# DEC4.net
KiCad netlist of a schematic drawn in EAGLE
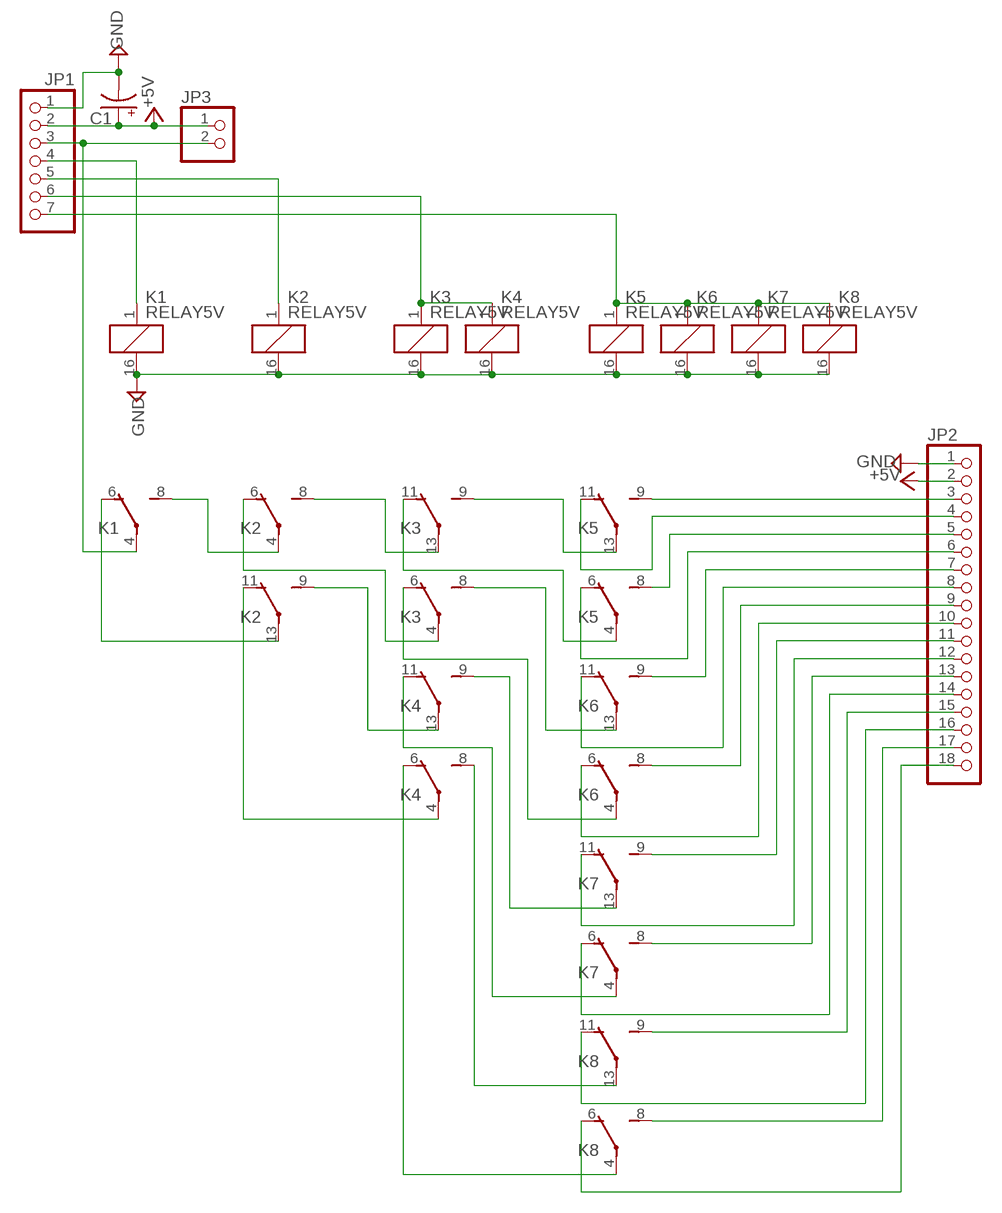
[diagram p0: schematic, sheet 1]

(export (version "E")
  (design (tool "Eeschema 10.0.6"))
  (components
    (comp (ref "C1")
      (value "CC-5-8.5")
      (footprint "eagle-import:E5-8,5")
      (libsource (lib "eagle-import") (part "CC-5-8.5"))
    )
    (comp (ref "JP1")
      (value "PINHD-1X7")
      (footprint "eagle-import:1X07")
      (libsource (lib "eagle-import") (part "PINHD-1X7"))
    )
    (comp (ref "JP2")
      (value "PINHD-1X18")
      (footprint "eagle-import:1X18")
      (libsource (lib "eagle-import") (part "PINHD-1X18"))
    )
    (comp (ref "JP3")
      (value "PINHD-1X2")
      (footprint "eagle-import:1X02")
      (libsource (lib "eagle-import") (part "PINHD-1X2"))
    )
    (comp (ref "K1")
      (value "RELAY5V")
      (footprint "eagle-import:DS-BT")
      (libsource (lib "eagle-import") (part "RELAY5V"))
    )
    (comp (ref "K2")
      (value "RELAY5V")
      (footprint "eagle-import:DS-BT")
      (libsource (lib "eagle-import") (part "RELAY5V"))
    )
    (comp (ref "K3")
      (value "RELAY5V")
      (footprint "eagle-import:DS-BT")
      (libsource (lib "eagle-import") (part "RELAY5V"))
    )
    (comp (ref "K4")
      (value "RELAY5V")
      (footprint "eagle-import:DS-BT")
      (libsource (lib "eagle-import") (part "RELAY5V"))
    )
    (comp (ref "K5")
      (value "RELAY5V")
      (footprint "eagle-import:DS-BT")
      (libsource (lib "eagle-import") (part "RELAY5V"))
    )
    (comp (ref "K6")
      (value "RELAY5V")
      (footprint "eagle-import:DS-BT")
      (libsource (lib "eagle-import") (part "RELAY5V"))
    )
    (comp (ref "K7")
      (value "RELAY5V")
      (footprint "eagle-import:DS-BT")
      (libsource (lib "eagle-import") (part "RELAY5V"))
    )
    (comp (ref "K8")
      (value "RELAY5V")
      (footprint "eagle-import:DS-BT")
      (libsource (lib "eagle-import") (part "RELAY5V"))
    )
  )
  (nets
    (net (code "1") (name "+5V") (class "Default")
      (node (ref "C1") (pin "+") (pinfunction "+_+") (pintype "passive"))
      (node (ref "JP1") (pin "2") (pinfunction "2_2") (pintype "passive"))
      (node (ref "JP2") (pin "2") (pinfunction "2_2") (pintype "passive"))
      (node (ref "JP3") (pin "1") (pinfunction "1_1") (pintype "passive"))
    )
    (net (code "2") (name "GND") (class "Default")
      (node (ref "C1") (pin "-") (pinfunction "-_-") (pintype "passive"))
      (node (ref "JP1") (pin "1") (pinfunction "1_1") (pintype "passive"))
      (node (ref "JP2") (pin "1") (pinfunction "1_1") (pintype "passive"))
      (node (ref "K1") (pin "16") (pinfunction "-_16") (pintype "passive"))
      (node (ref "K2") (pin "16") (pinfunction "-_16") (pintype "passive"))
      (node (ref "K3") (pin "16") (pinfunction "-_16") (pintype "passive"))
      (node (ref "K4") (pin "16") (pinfunction "-_16") (pintype "passive"))
      (node (ref "K5") (pin "16") (pinfunction "-_16") (pintype "passive"))
      (node (ref "K6") (pin "16") (pinfunction "-_16") (pintype "passive"))
      (node (ref "K7") (pin "16") (pinfunction "-_16") (pintype "passive"))
      (node (ref "K8") (pin "16") (pinfunction "-_16") (pintype "passive"))
    )
    (net (code "3") (name "Net-(K1A-+)") (class "Default")
      (node (ref "JP1") (pin "4") (pinfunction "4_4") (pintype "passive"))
      (node (ref "K1") (pin "1") (pinfunction "+_1") (pintype "passive"))
    )
    (net (code "4") (name "Net-(K1B-O)") (class "Default")
      (node (ref "K1") (pin "6") (pinfunction "O_6") (pintype "passive"))
      (node (ref "K2") (pin "13") (pinfunction "P_13") (pintype "passive"))
    )
    (net (code "5") (name "Net-(K1B-P)") (class "Default")
      (node (ref "JP1") (pin "3") (pinfunction "3_3") (pintype "passive"))
      (node (ref "JP3") (pin "2") (pinfunction "2_2") (pintype "passive"))
      (node (ref "K1") (pin "4") (pinfunction "P_4") (pintype "passive"))
    )
    (net (code "6") (name "Net-(K1B-S)") (class "Default")
      (node (ref "K1") (pin "8") (pinfunction "S_8") (pintype "passive"))
      (node (ref "K2") (pin "4") (pinfunction "P_4") (pintype "passive"))
    )
    (net (code "7") (name "Net-(K2A-+)") (class "Default")
      (node (ref "JP1") (pin "5") (pinfunction "5_5") (pintype "passive"))
      (node (ref "K2") (pin "1") (pinfunction "+_1") (pintype "passive"))
    )
    (net (code "8") (name "Net-(K2B-O)") (class "Default")
      (node (ref "K2") (pin "6") (pinfunction "O_6") (pintype "passive"))
      (node (ref "K3") (pin "4") (pinfunction "P_4") (pintype "passive"))
    )
    (net (code "9") (name "Net-(K2B-S)") (class "Default")
      (node (ref "K2") (pin "8") (pinfunction "S_8") (pintype "passive"))
      (node (ref "K3") (pin "13") (pinfunction "P_13") (pintype "passive"))
    )
    (net (code "10") (name "Net-(K2C-O)") (class "Default")
      (node (ref "K2") (pin "11") (pinfunction "O_11") (pintype "passive"))
      (node (ref "K4") (pin "4") (pinfunction "P_4") (pintype "passive"))
    )
    (net (code "11") (name "Net-(K2C-S)") (class "Default")
      (node (ref "K2") (pin "9") (pinfunction "S_9") (pintype "passive"))
      (node (ref "K4") (pin "13") (pinfunction "P_13") (pintype "passive"))
    )
    (net (code "12") (name "Net-(K3A-+)") (class "Default")
      (node (ref "JP1") (pin "6") (pinfunction "6_6") (pintype "passive"))
      (node (ref "K3") (pin "1") (pinfunction "+_1") (pintype "passive"))
      (node (ref "K4") (pin "1") (pinfunction "+_1") (pintype "passive"))
    )
    (net (code "13") (name "Net-(K3B-O)") (class "Default")
      (node (ref "K3") (pin "6") (pinfunction "O_6") (pintype "passive"))
      (node (ref "K6") (pin "4") (pinfunction "P_4") (pintype "passive"))
    )
    (net (code "14") (name "Net-(K3B-S)") (class "Default")
      (node (ref "K3") (pin "8") (pinfunction "S_8") (pintype "passive"))
      (node (ref "K6") (pin "13") (pinfunction "P_13") (pintype "passive"))
    )
    (net (code "15") (name "Net-(K3C-O)") (class "Default")
      (node (ref "K3") (pin "11") (pinfunction "O_11") (pintype "passive"))
      (node (ref "K5") (pin "4") (pinfunction "P_4") (pintype "passive"))
    )
    (net (code "16") (name "Net-(K3C-S)") (class "Default")
      (node (ref "K3") (pin "9") (pinfunction "S_9") (pintype "passive"))
      (node (ref "K5") (pin "13") (pinfunction "P_13") (pintype "passive"))
    )
    (net (code "17") (name "Net-(K4B-O)") (class "Default")
      (node (ref "K4") (pin "6") (pinfunction "O_6") (pintype "passive"))
      (node (ref "K8") (pin "4") (pinfunction "P_4") (pintype "passive"))
    )
    (net (code "18") (name "Net-(K4B-S)") (class "Default")
      (node (ref "K4") (pin "8") (pinfunction "S_8") (pintype "passive"))
      (node (ref "K8") (pin "13") (pinfunction "P_13") (pintype "passive"))
    )
    (net (code "19") (name "Net-(K4C-O)") (class "Default")
      (node (ref "K4") (pin "11") (pinfunction "O_11") (pintype "passive"))
      (node (ref "K7") (pin "4") (pinfunction "P_4") (pintype "passive"))
    )
    (net (code "20") (name "Net-(K4C-S)") (class "Default")
      (node (ref "K4") (pin "9") (pinfunction "S_9") (pintype "passive"))
      (node (ref "K7") (pin "13") (pinfunction "P_13") (pintype "passive"))
    )
    (net (code "21") (name "Net-(K5A-+)") (class "Default")
      (node (ref "JP1") (pin "7") (pinfunction "7_7") (pintype "passive"))
      (node (ref "K5") (pin "1") (pinfunction "+_1") (pintype "passive"))
      (node (ref "K6") (pin "1") (pinfunction "+_1") (pintype "passive"))
      (node (ref "K7") (pin "1") (pinfunction "+_1") (pintype "passive"))
      (node (ref "K8") (pin "1") (pinfunction "+_1") (pintype "passive"))
    )
    (net (code "22") (name "Net-(K5B-O)") (class "Default")
      (node (ref "JP2") (pin "6") (pinfunction "6_6") (pintype "passive"))
      (node (ref "K5") (pin "6") (pinfunction "O_6") (pintype "passive"))
    )
    (net (code "23") (name "Net-(K5B-S)") (class "Default")
      (node (ref "JP2") (pin "5") (pinfunction "5_5") (pintype "passive"))
      (node (ref "K5") (pin "8") (pinfunction "S_8") (pintype "passive"))
    )
    (net (code "24") (name "Net-(K5C-O)") (class "Default")
      (node (ref "JP2") (pin "4") (pinfunction "4_4") (pintype "passive"))
      (node (ref "K5") (pin "11") (pinfunction "O_11") (pintype "passive"))
    )
    (net (code "25") (name "Net-(K5C-S)") (class "Default")
      (node (ref "JP2") (pin "3") (pinfunction "3_3") (pintype "passive"))
      (node (ref "K5") (pin "9") (pinfunction "S_9") (pintype "passive"))
    )
    (net (code "26") (name "Net-(K6B-O)") (class "Default")
      (node (ref "JP2") (pin "10") (pinfunction "10_10") (pintype "passive"))
      (node (ref "K6") (pin "6") (pinfunction "O_6") (pintype "passive"))
    )
    (net (code "27") (name "Net-(K6B-S)") (class "Default")
      (node (ref "JP2") (pin "9") (pinfunction "9_9") (pintype "passive"))
      (node (ref "K6") (pin "8") (pinfunction "S_8") (pintype "passive"))
    )
    (net (code "28") (name "Net-(K6C-O)") (class "Default")
      (node (ref "JP2") (pin "8") (pinfunction "8_8") (pintype "passive"))
      (node (ref "K6") (pin "11") (pinfunction "O_11") (pintype "passive"))
    )
    (net (code "29") (name "Net-(K6C-S)") (class "Default")
      (node (ref "JP2") (pin "7") (pinfunction "7_7") (pintype "passive"))
      (node (ref "K6") (pin "9") (pinfunction "S_9") (pintype "passive"))
    )
    (net (code "30") (name "Net-(K7B-O)") (class "Default")
      (node (ref "JP2") (pin "14") (pinfunction "14_14") (pintype "passive"))
      (node (ref "K7") (pin "6") (pinfunction "O_6") (pintype "passive"))
    )
    (net (code "31") (name "Net-(K7B-S)") (class "Default")
      (node (ref "JP2") (pin "13") (pinfunction "13_13") (pintype "passive"))
      (node (ref "K7") (pin "8") (pinfunction "S_8") (pintype "passive"))
    )
    (net (code "32") (name "Net-(K7C-O)") (class "Default")
      (node (ref "JP2") (pin "12") (pinfunction "12_12") (pintype "passive"))
      (node (ref "K7") (pin "11") (pinfunction "O_11") (pintype "passive"))
    )
    (net (code "33") (name "Net-(K7C-S)") (class "Default")
      (node (ref "JP2") (pin "11") (pinfunction "11_11") (pintype "passive"))
      (node (ref "K7") (pin "9") (pinfunction "S_9") (pintype "passive"))
    )
    (net (code "34") (name "Net-(K8B-O)") (class "Default")
      (node (ref "JP2") (pin "18") (pinfunction "18_18") (pintype "passive"))
      (node (ref "K8") (pin "6") (pinfunction "O_6") (pintype "passive"))
    )
    (net (code "35") (name "Net-(K8B-S)") (class "Default")
      (node (ref "JP2") (pin "17") (pinfunction "17_17") (pintype "passive"))
      (node (ref "K8") (pin "8") (pinfunction "S_8") (pintype "passive"))
    )
    (net (code "36") (name "Net-(K8C-O)") (class "Default")
      (node (ref "JP2") (pin "16") (pinfunction "16_16") (pintype "passive"))
      (node (ref "K8") (pin "11") (pinfunction "O_11") (pintype "passive"))
    )
    (net (code "37") (name "Net-(K8C-S)") (class "Default")
      (node (ref "JP2") (pin "15") (pinfunction "15_15") (pintype "passive"))
      (node (ref "K8") (pin "9") (pinfunction "S_9") (pintype "passive"))
    )
  )
)
